# MXR4_v1.net
KiCad netlist of a schematic drawn in EAGLE
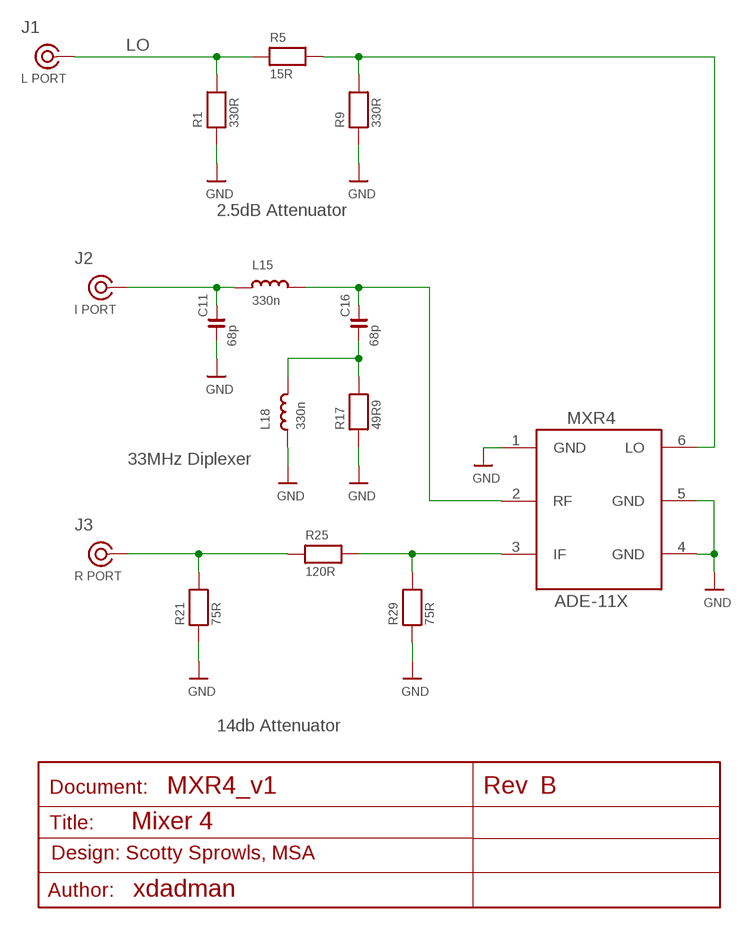
[diagram p0: schematic, sheet 1]

(export (version "E")
  (design (tool "Eeschema 10.0.6"))
  (components
    (comp (ref "C11")
      (value "68p")
      (footprint "eagle-import:C0805")
      (libsource (lib "eagle-import") (part "C080568P"))
    )
    (comp (ref "C16")
      (value "68p")
      (footprint "eagle-import:C0805")
      (libsource (lib "eagle-import") (part "C080568P"))
    )
    (comp (ref "J1")
      (value "L PORT")
      (footprint "eagle-import:SLIM_COAX_PAD")
      (libsource (lib "eagle-import") (part "COAX"))
    )
    (comp (ref "J2")
      (value "I PORT")
      (footprint "eagle-import:SLIM_COAX_PAD")
      (libsource (lib "eagle-import") (part "COAX"))
    )
    (comp (ref "J3")
      (value "R PORT")
      (footprint "eagle-import:SLIM_COAX_PAD")
      (libsource (lib "eagle-import") (part "COAX"))
    )
    (comp (ref "L15")
      (value "330n")
      (footprint "eagle-import:L805")
      (libsource (lib "eagle-import") (part "L0805330N"))
    )
    (comp (ref "L18")
      (value "330n")
      (footprint "eagle-import:L805")
      (libsource (lib "eagle-import") (part "L0805330N"))
    )
    (comp (ref "MXR4")
      (value "ADE-11X")
      (footprint "eagle-import:ADE-11X")
      (libsource (lib "eagle-import") (part "ADE-11X"))
    )
    (comp (ref "R1")
      (value "330R")
      (footprint "eagle-import:R0805")
      (libsource (lib "eagle-import") (part "R0805330R"))
    )
    (comp (ref "R5")
      (value "15R")
      (footprint "eagle-import:0805")
      (libsource (lib "eagle-import") (part "R080515R"))
    )
    (comp (ref "R9")
      (value "330R")
      (footprint "eagle-import:R0805")
      (libsource (lib "eagle-import") (part "R0805330R"))
    )
    (comp (ref "R17")
      (value "49R9")
      (footprint "eagle-import:R0805")
      (libsource (lib "eagle-import") (part "R080549R9"))
    )
    (comp (ref "R21")
      (value "75R")
      (footprint "eagle-import:R0805")
      (libsource (lib "eagle-import") (part "R080575R"))
    )
    (comp (ref "R25")
      (value "120R")
      (footprint "eagle-import:R0805")
      (libsource (lib "eagle-import") (part "R0805120R"))
    )
    (comp (ref "R29")
      (value "75R")
      (footprint "eagle-import:R0805")
      (libsource (lib "eagle-import") (part "R080575R"))
    )
  )
  (nets
    (net (code "1") (name "/LO") (class "Default")
      (node (ref "J1") (pin "SIG") (pinfunction "1_SIG") (pintype "passive"))
      (node (ref "R1") (pin "2") (pinfunction "2_2") (pintype "passive"))
      (node (ref "R5") (pin "1") (pinfunction "1_1") (pintype "passive"))
    )
    (net (code "2") (name "GND") (class "Default")
      (node (ref "C11") (pin "1") (pinfunction "1_1") (pintype "passive"))
      (node (ref "L18") (pin "1") (pinfunction "1_1") (pintype "passive"))
      (node (ref "MXR4") (pin "1") (pinfunction "GND_1") (pintype "bidirectional"))
      (node (ref "MXR4") (pin "4") (pinfunction "GND_4") (pintype "bidirectional"))
      (node (ref "MXR4") (pin "5") (pinfunction "GND_5") (pintype "bidirectional"))
      (node (ref "R1") (pin "1") (pinfunction "1_1") (pintype "passive"))
      (node (ref "R17") (pin "1") (pinfunction "1_1") (pintype "passive"))
      (node (ref "R21") (pin "1") (pinfunction "1_1") (pintype "passive"))
      (node (ref "R29") (pin "1") (pinfunction "1_1") (pintype "passive"))
      (node (ref "R9") (pin "1") (pinfunction "1_1") (pintype "passive"))
    )
    (net (code "3") (name "Net-(C16-Pad1)") (class "Default")
      (node (ref "C16") (pin "1") (pinfunction "1_1") (pintype "passive"))
      (node (ref "L18") (pin "2") (pinfunction "2_2") (pintype "passive"))
      (node (ref "R17") (pin "2") (pinfunction "2_2") (pintype "passive"))
    )
    (net (code "4") (name "Net-(J2A-1)") (class "Default")
      (node (ref "C11") (pin "2") (pinfunction "2_2") (pintype "passive"))
      (node (ref "J2") (pin "SIG") (pinfunction "1_SIG") (pintype "passive"))
      (node (ref "L15") (pin "1") (pinfunction "1_1") (pintype "passive"))
    )
    (net (code "5") (name "Net-(J3A-1)") (class "Default")
      (node (ref "J3") (pin "SIG") (pinfunction "1_SIG") (pintype "passive"))
      (node (ref "R21") (pin "2") (pinfunction "2_2") (pintype "passive"))
      (node (ref "R25") (pin "1") (pinfunction "1_1") (pintype "passive"))
    )
    (net (code "6") (name "Net-(MXR4-IF)") (class "Default")
      (node (ref "MXR4") (pin "3") (pinfunction "IF_3") (pintype "bidirectional"))
      (node (ref "R25") (pin "2") (pinfunction "2_2") (pintype "passive"))
      (node (ref "R29") (pin "2") (pinfunction "2_2") (pintype "passive"))
    )
    (net (code "7") (name "Net-(MXR4-LO)") (class "Default")
      (node (ref "MXR4") (pin "6") (pinfunction "LO_6") (pintype "bidirectional"))
      (node (ref "R5") (pin "2") (pinfunction "2_2") (pintype "passive"))
      (node (ref "R9") (pin "2") (pinfunction "2_2") (pintype "passive"))
    )
    (net (code "8") (name "Net-(MXR4-RF)") (class "Default")
      (node (ref "C16") (pin "2") (pinfunction "2_2") (pintype "passive"))
      (node (ref "L15") (pin "2") (pinfunction "2_2") (pintype "passive"))
      (node (ref "MXR4") (pin "2") (pinfunction "RF_2") (pintype "bidirectional"))
    )
  )
)
